# Starlings_Technology_nrf52.net
KiCad netlist of a schematic drawn in EAGLE
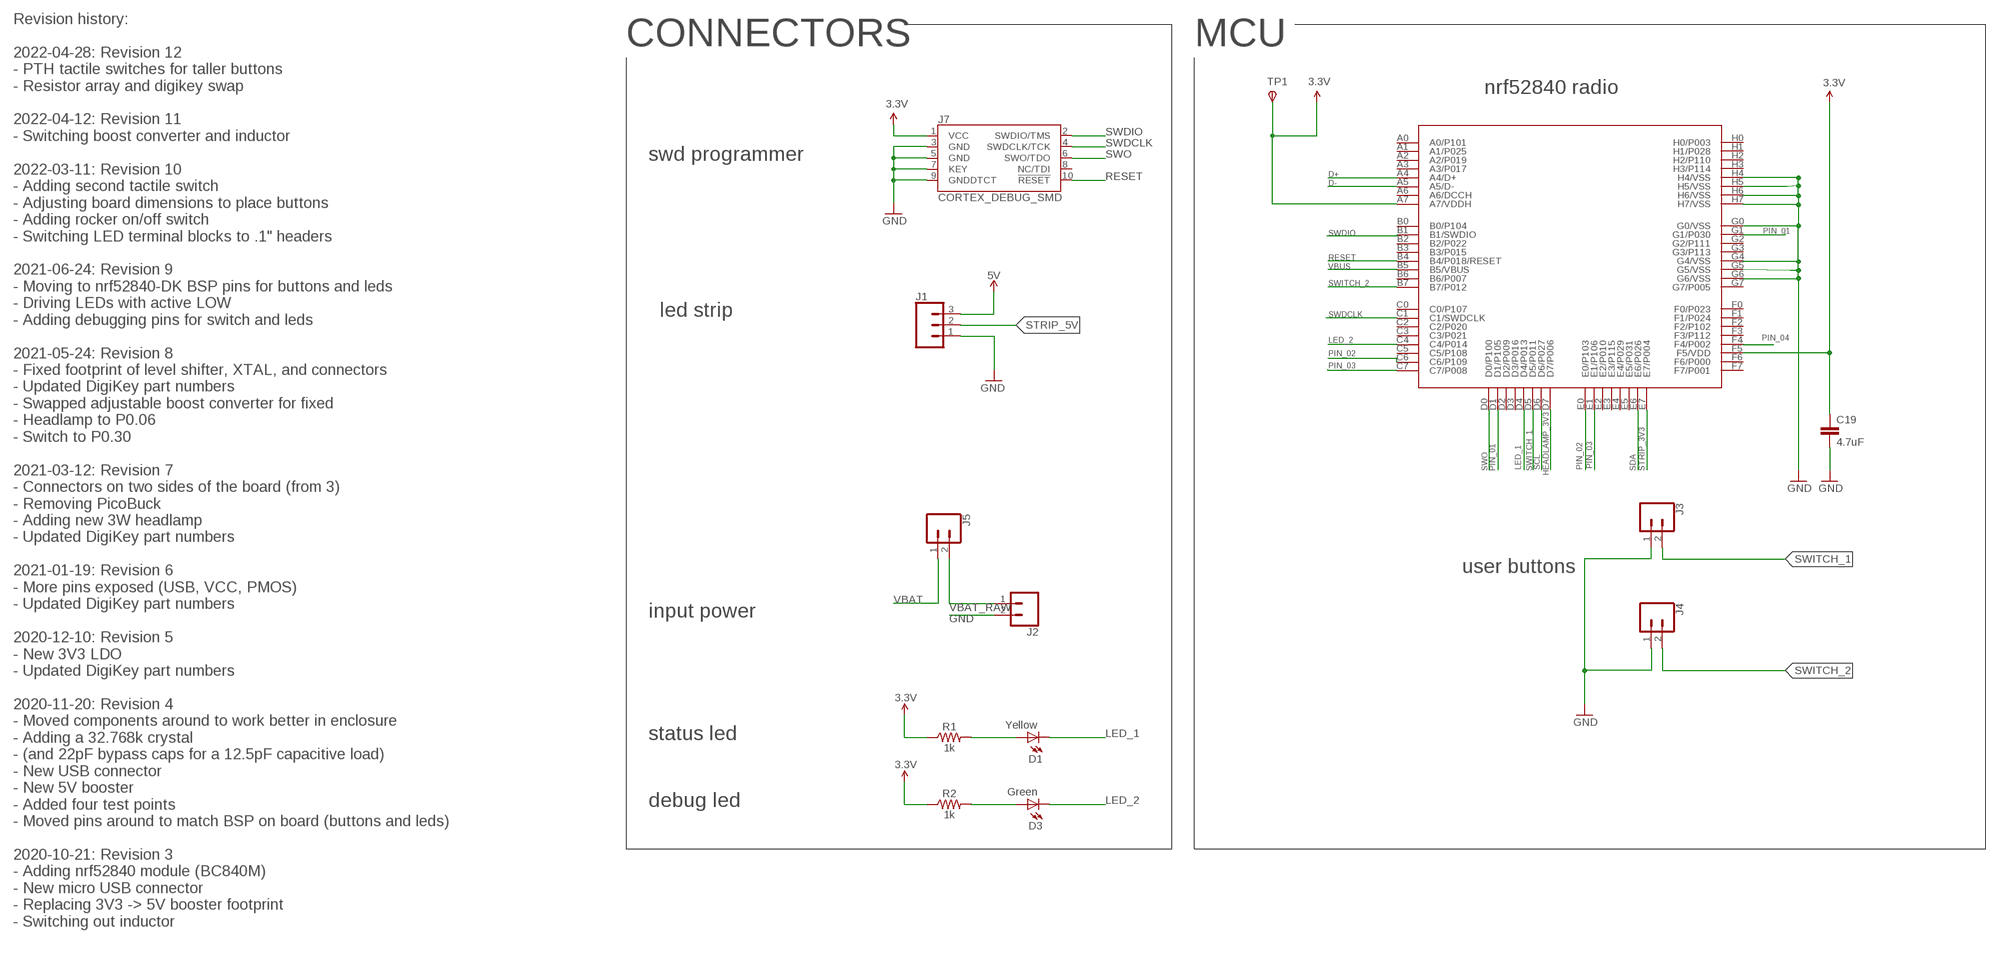
[diagram p0: schematic, sheet 1, part 1 of 2]
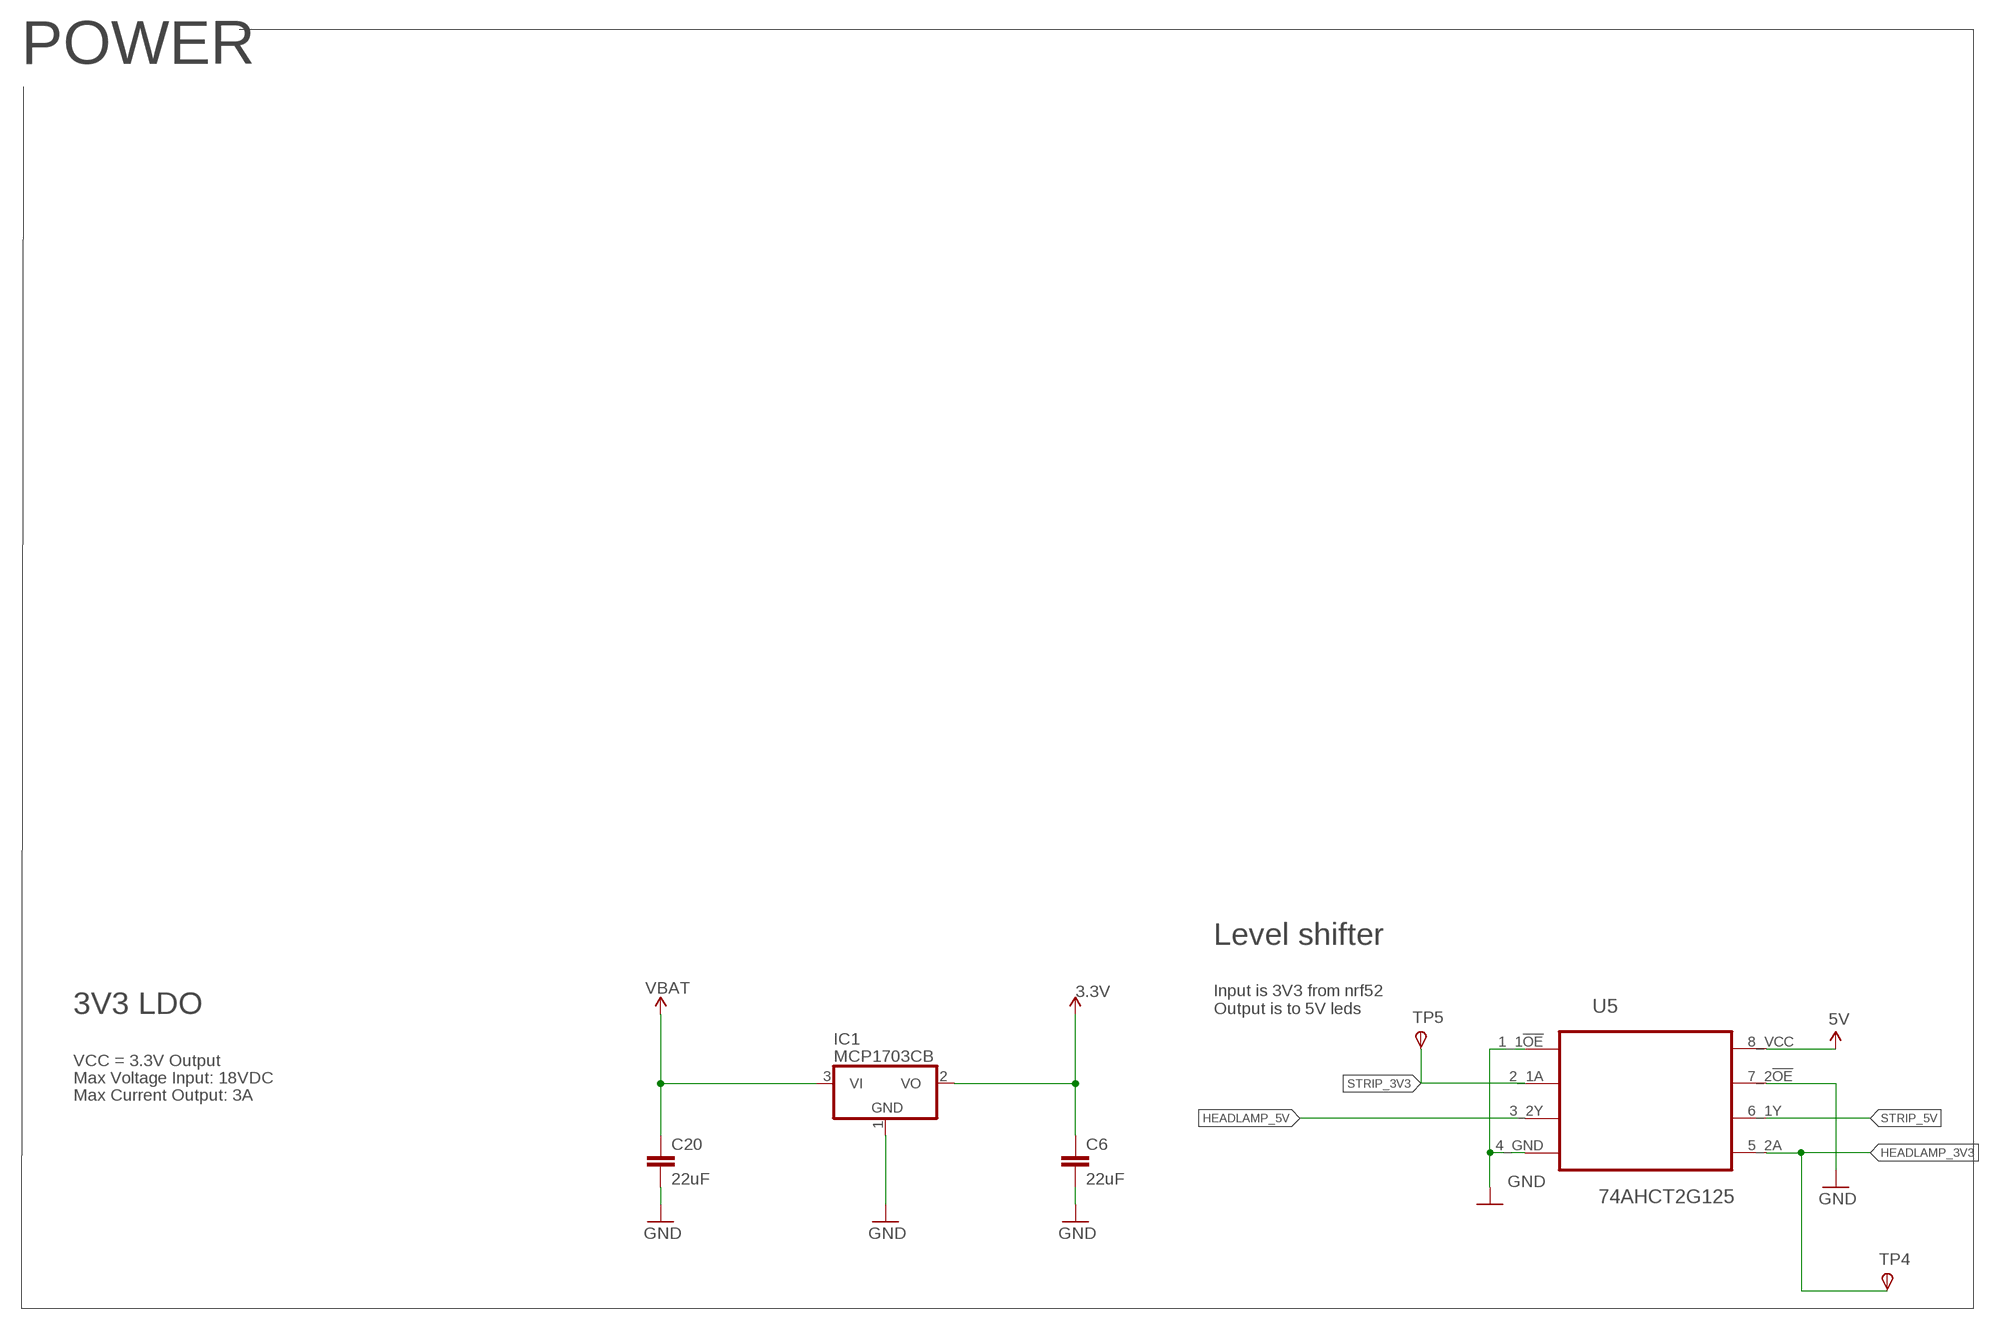
[diagram p1: schematic, sheet 1, part 2 of 2]

(export (version "E")
  (design (tool "Eeschema 10.0.6"))
  (components
    (comp (ref "C6")
      (value "22uF")
      (footprint "eagle-import:0805")
      (libsource (lib "eagle-import") (part "22UF-0805-6.3V-20%"))
    )
    (comp (ref "C19")
      (value "4.7uF")
      (footprint "eagle-import:0603")
      (libsource (lib "eagle-import") (part "4.7UF0603"))
    )
    (comp (ref "C20")
      (value "22uF")
      (footprint "eagle-import:0805")
      (libsource (lib "eagle-import") (part "22UF-0805-6.3V-20%"))
    )
    (comp (ref "D1")
      (value "Yellow")
      (footprint "eagle-import:LED-0603")
      (libsource (lib "eagle-import") (part "LED0603"))
    )
    (comp (ref "D3")
      (value "Green")
      (footprint "eagle-import:LED-0603")
      (libsource (lib "eagle-import") (part "LED0603"))
    )
    (comp (ref "IC1")
      (value "MCP1703CB")
      (footprint "eagle-import:SOT23")
      (libsource (lib "eagle-import") (part "MCP1703CB"))
    )
    (comp (ref "J1")
      (value "CONN_03LOCK_LONGPADS")
      (footprint "eagle-import:1X03_LOCK_LONGPADS")
      (libsource (lib "eagle-import") (part "CONN_03LOCK_LONGPADS"))
    )
    (comp (ref "J2")
      (value "CONN_02LOCK_LONGPADS")
      (footprint "eagle-import:1X02_LOCK_LONGPADS")
      (libsource (lib "eagle-import") (part "CONN_02LOCK_LONGPADS"))
    )
    (comp (ref "J3")
      (value "CONN_02LOCK_LONGPADS")
      (footprint "eagle-import:1X02_LOCK_LONGPADS")
      (libsource (lib "eagle-import") (part "CONN_02LOCK_LONGPADS"))
    )
    (comp (ref "J4")
      (value "CONN_02LOCK_LONGPADS")
      (footprint "eagle-import:1X02_LOCK_LONGPADS")
      (libsource (lib "eagle-import") (part "CONN_02LOCK_LONGPADS"))
    )
    (comp (ref "J5")
      (value "CONN_02LOCK_LONGPADS")
      (footprint "eagle-import:1X02_LOCK_LONGPADS")
      (libsource (lib "eagle-import") (part "CONN_02LOCK_LONGPADS"))
    )
    (comp (ref "J7")
      (value "CORTEX_DEBUG_SMD")
      (footprint "eagle-import:SAMTECH_FTSH-105-01")
      (libsource (lib "eagle-import") (part "CORTEX_DEBUG_SMD"))
    )
    (comp (ref "R1")
      (value "1k")
      (footprint "eagle-import:0603")
      (libsource (lib "eagle-import") (part "1KOHM-0603-1/10W-1%"))
    )
    (comp (ref "R2")
      (value "1k")
      (footprint "eagle-import:0603")
      (libsource (lib "eagle-import") (part "1KOHM-0603-1/10W-1%"))
    )
    (comp (ref "TP1")
      (value "TPSB1,27")
      (footprint "eagle-import:B1,27")
      (libsource (lib "eagle-import") (part "TPSB1,27"))
    )
    (comp (ref "TP4")
      (value "TPSB1,27")
      (footprint "eagle-import:B1,27")
      (libsource (lib "eagle-import") (part "TPSB1,27"))
    )
    (comp (ref "TP5")
      (value "TPSB1,27")
      (footprint "eagle-import:B1,27")
      (libsource (lib "eagle-import") (part "TPSB1,27"))
    )
    (comp (ref "U3")
      (value "BC840M")
      (footprint "eagle-import:BC840M")
      (libsource (lib "eagle-import") (part "BC840M"))
    )
    (comp (ref "U5")
      (value "74AHCT2G125")
      (footprint "eagle-import:VSSOP-8")
      (fields (field (name "MPN") "PCA9306DC,125"))
      (libsource (lib "eagle-import") (part "VSSOP-8_DEVICE"))
    )
  )
  (nets
    (net (code "1") (name "/D+") (class "Default")
      (node (ref "U3") (pin "A4") (pinfunction "A4/D+_A4") (pintype "bidirectional"))
    )
    (net (code "2") (name "/D-") (class "Default")
      (node (ref "U3") (pin "A5") (pinfunction "A5/D-_A5") (pintype "bidirectional"))
    )
    (net (code "3") (name "/LED_1") (class "Default")
      (node (ref "D1") (pin "C") (pinfunction "C_C") (pintype "passive"))
      (node (ref "U3") (pin "D4") (pinfunction "D4/P013_D4") (pintype "bidirectional"))
    )
    (net (code "4") (name "/LED_2") (class "Default")
      (node (ref "D3") (pin "C") (pinfunction "C_C") (pintype "passive"))
      (node (ref "U3") (pin "C4") (pinfunction "C4/P014_C4") (pintype "bidirectional"))
    )
    (net (code "5") (name "/PIN_01") (class "Default")
      (node (ref "U3") (pin "D1") (pinfunction "D1/P105_D1") (pintype "bidirectional"))
      (node (ref "U3") (pin "G1") (pinfunction "G1/P030_G1") (pintype "bidirectional"))
    )
    (net (code "6") (name "/PIN_02") (class "Default")
      (node (ref "U3") (pin "C6") (pinfunction "C6/P109_C6") (pintype "bidirectional"))
      (node (ref "U3") (pin "E0") (pinfunction "E0/P103_E0") (pintype "bidirectional"))
    )
    (net (code "7") (name "/PIN_03") (class "Default")
      (node (ref "U3") (pin "C7") (pinfunction "C7/P008_C7") (pintype "bidirectional"))
      (node (ref "U3") (pin "E1") (pinfunction "E1/P106_E1") (pintype "bidirectional"))
    )
    (net (code "8") (name "/PIN_04") (class "Default")
      (node (ref "U3") (pin "F4") (pinfunction "F4/P002_F4") (pintype "bidirectional"))
    )
    (net (code "9") (name "/RESET") (class "Default")
      (node (ref "J7") (pin "10") (pinfunction "~{RESET}_10") (pintype "bidirectional"))
      (node (ref "U3") (pin "B4") (pinfunction "B4/P018/RESET_B4") (pintype "bidirectional"))
    )
    (net (code "10") (name "/SCL") (class "Default")
      (node (ref "U3") (pin "D6") (pinfunction "D6/P027_D6") (pintype "bidirectional"))
    )
    (net (code "11") (name "/SDA") (class "Default")
      (node (ref "U3") (pin "E6") (pinfunction "E6/P026_E6") (pintype "bidirectional"))
    )
    (net (code "12") (name "/SWDCLK") (class "Default")
      (node (ref "J7") (pin "4") (pinfunction "SWDCLK/TCK_4") (pintype "bidirectional"))
      (node (ref "U3") (pin "C1") (pinfunction "C1/SWDCLK_C1") (pintype "bidirectional"))
    )
    (net (code "13") (name "/SWDIO") (class "Default")
      (node (ref "J7") (pin "2") (pinfunction "SWDIO/TMS_2") (pintype "bidirectional"))
      (node (ref "U3") (pin "B1") (pinfunction "B1/SWDIO_B1") (pintype "bidirectional"))
    )
    (net (code "14") (name "/SWO") (class "Default")
      (node (ref "J7") (pin "6") (pinfunction "SWO/TDO_6") (pintype "bidirectional"))
      (node (ref "U3") (pin "D0") (pinfunction "D0/P100_D0") (pintype "bidirectional"))
    )
    (net (code "15") (name "/VBAT_RAW") (class "Default")
      (node (ref "J2") (pin "1") (pinfunction "1_1") (pintype "passive"))
      (node (ref "J5") (pin "2") (pinfunction "2_2") (pintype "passive"))
    )
    (net (code "16") (name "/VBUS") (class "Default")
      (node (ref "U3") (pin "B5") (pinfunction "B5/VBUS_B5") (pintype "bidirectional"))
    )
    (net (code "17") (name "3.3V") (class "Default")
      (node (ref "C19") (pin "1") (pinfunction "1_1") (pintype "passive"))
      (node (ref "C6") (pin "1") (pinfunction "1_1") (pintype "passive"))
      (node (ref "IC1") (pin "2") (pinfunction "VO_2") (pintype "passive"))
      (node (ref "J7") (pin "1") (pinfunction "VCC_1") (pintype "bidirectional"))
      (node (ref "R1") (pin "1") (pinfunction "1_1") (pintype "passive"))
      (node (ref "R2") (pin "1") (pinfunction "1_1") (pintype "passive"))
      (node (ref "TP1") (pin "TP") (pinfunction "PP_TP") (pintype "input"))
      (node (ref "U3") (pin "A7") (pinfunction "A7/VDDH_A7") (pintype "bidirectional"))
      (node (ref "U3") (pin "F5") (pinfunction "F5/VDD_F5") (pintype "bidirectional"))
    )
    (net (code "18") (name "5V") (class "Default")
      (node (ref "J1") (pin "3") (pinfunction "3_3") (pintype "passive"))
      (node (ref "U5") (pin "8_VCC") (pinfunction "8_8_VCC") (pintype "bidirectional"))
    )
    (net (code "19") (name "GND") (class "Default")
      (node (ref "C19") (pin "2") (pinfunction "2_2") (pintype "passive"))
      (node (ref "C20") (pin "2") (pinfunction "2_2") (pintype "passive"))
      (node (ref "C6") (pin "2") (pinfunction "2_2") (pintype "passive"))
      (node (ref "IC1") (pin "1") (pinfunction "GND_1") (pintype "passive"))
      (node (ref "J1") (pin "1") (pinfunction "1_1") (pintype "passive"))
      (node (ref "J2") (pin "2") (pinfunction "2_2") (pintype "passive"))
      (node (ref "J3") (pin "1") (pinfunction "1_1") (pintype "passive"))
      (node (ref "J4") (pin "1") (pinfunction "1_1") (pintype "passive"))
      (node (ref "J7") (pin "3") (pinfunction "GND_3") (pintype "bidirectional"))
      (node (ref "J7") (pin "5") (pinfunction "GND_5") (pintype "bidirectional"))
      (node (ref "J7") (pin "7") (pinfunction "KEY_7") (pintype "bidirectional"))
      (node (ref "J7") (pin "9") (pinfunction "GNDDTCT_9") (pintype "bidirectional"))
      (node (ref "U3") (pin "G0") (pinfunction "G0/VSS_G0") (pintype "bidirectional"))
      (node (ref "U3") (pin "G4") (pinfunction "G4/VSS_G4") (pintype "bidirectional"))
      (node (ref "U3") (pin "G5") (pinfunction "G5/VSS_G5") (pintype "bidirectional"))
      (node (ref "U3") (pin "G6") (pinfunction "G6/VSS_G6") (pintype "bidirectional"))
      (node (ref "U3") (pin "H4") (pinfunction "H4/VSS_H4") (pintype "bidirectional"))
      (node (ref "U3") (pin "H5") (pinfunction "H5/VSS_H5") (pintype "bidirectional"))
      (node (ref "U3") (pin "H6") (pinfunction "H6/VSS_H6") (pintype "bidirectional"))
      (node (ref "U3") (pin "H7") (pinfunction "H7/VSS_H7") (pintype "bidirectional"))
      (node (ref "U5") (pin "1_1!OE") (pinfunction "1_1_1!OE") (pintype "bidirectional"))
      (node (ref "U5") (pin "4_GND") (pinfunction "4_4_GND") (pintype "bidirectional"))
      (node (ref "U5") (pin "7_2!OE") (pinfunction "7_7_2!OE") (pintype "bidirectional"))
    )
    (net (code "20") (name "HEADLAMP_3V3") (class "Default")
      (node (ref "TP4") (pin "TP") (pinfunction "PP_TP") (pintype "input"))
      (node (ref "U3") (pin "D7") (pinfunction "D7/P006_D7") (pintype "bidirectional"))
      (node (ref "U5") (pin "5_2A") (pinfunction "5_5_2A") (pintype "bidirectional"))
    )
    (net (code "21") (name "HEADLAMP_5V") (class "Default")
      (node (ref "U5") (pin "3_2Y") (pinfunction "3_3_2Y") (pintype "bidirectional"))
    )
    (net (code "22") (name "Net-(D1-PadA)") (class "Default")
      (node (ref "D1") (pin "A") (pinfunction "A_A") (pintype "passive"))
      (node (ref "R1") (pin "2") (pinfunction "2_2") (pintype "passive"))
    )
    (net (code "23") (name "Net-(D3-PadA)") (class "Default")
      (node (ref "D3") (pin "A") (pinfunction "A_A") (pintype "passive"))
      (node (ref "R2") (pin "2") (pinfunction "2_2") (pintype "passive"))
    )
    (net (code "24") (name "STRIP_3V3") (class "Default")
      (node (ref "TP5") (pin "TP") (pinfunction "PP_TP") (pintype "input"))
      (node (ref "U3") (pin "E7") (pinfunction "E7/P004_E7") (pintype "bidirectional"))
      (node (ref "U5") (pin "2_1A") (pinfunction "2_2_1A") (pintype "bidirectional"))
    )
    (net (code "25") (name "STRIP_5V") (class "Default")
      (node (ref "J1") (pin "2") (pinfunction "2_2") (pintype "passive"))
      (node (ref "U5") (pin "6_1Y") (pinfunction "6_6_1Y") (pintype "bidirectional"))
    )
    (net (code "26") (name "SWITCH_1") (class "Default")
      (node (ref "J3") (pin "2") (pinfunction "2_2") (pintype "passive"))
      (node (ref "U3") (pin "D5") (pinfunction "D5/P011_D5") (pintype "bidirectional"))
    )
    (net (code "27") (name "SWITCH_2") (class "Default")
      (node (ref "J4") (pin "2") (pinfunction "2_2") (pintype "passive"))
      (node (ref "U3") (pin "B7") (pinfunction "B7/P012_B7") (pintype "bidirectional"))
    )
    (net (code "28") (name "VBAT") (class "Default")
      (node (ref "C20") (pin "1") (pinfunction "1_1") (pintype "passive"))
      (node (ref "IC1") (pin "3") (pinfunction "VI_3") (pintype "input"))
      (node (ref "J5") (pin "1") (pinfunction "1_1") (pintype "passive"))
    )
    (net (code "29") (name "unconnected-(J7-NC{slash}TDI-Pad8)") (class "Default")
      (node (ref "J7") (pin "8") (pinfunction "NC/TDI_8") (pintype "bidirectional"))
    )
    (net (code "30") (name "unconnected-(U3-A0{slash}P101-PadA0)") (class "Default")
      (node (ref "U3") (pin "A0") (pinfunction "A0/P101_A0") (pintype "bidirectional"))
    )
    (net (code "31") (name "unconnected-(U3-A1{slash}P025-PadA1)") (class "Default")
      (node (ref "U3") (pin "A1") (pinfunction "A1/P025_A1") (pintype "bidirectional"))
    )
    (net (code "32") (name "unconnected-(U3-A2{slash}P019-PadA2)") (class "Default")
      (node (ref "U3") (pin "A2") (pinfunction "A2/P019_A2") (pintype "bidirectional"))
    )
    (net (code "33") (name "unconnected-(U3-A3{slash}P017-PadA3)") (class "Default")
      (node (ref "U3") (pin "A3") (pinfunction "A3/P017_A3") (pintype "bidirectional"))
    )
    (net (code "34") (name "unconnected-(U3-A6{slash}DCCH-PadA6)") (class "Default")
      (node (ref "U3") (pin "A6") (pinfunction "A6/DCCH_A6") (pintype "bidirectional"))
    )
    (net (code "35") (name "unconnected-(U3-B0{slash}P104-PadB0)") (class "Default")
      (node (ref "U3") (pin "B0") (pinfunction "B0/P104_B0") (pintype "bidirectional"))
    )
    (net (code "36") (name "unconnected-(U3-B2{slash}P022-PadB2)") (class "Default")
      (node (ref "U3") (pin "B2") (pinfunction "B2/P022_B2") (pintype "bidirectional"))
    )
    (net (code "37") (name "unconnected-(U3-B3{slash}P015-PadB3)") (class "Default")
      (node (ref "U3") (pin "B3") (pinfunction "B3/P015_B3") (pintype "bidirectional"))
    )
    (net (code "38") (name "unconnected-(U3-B6{slash}P007-PadB6)") (class "Default")
      (node (ref "U3") (pin "B6") (pinfunction "B6/P007_B6") (pintype "bidirectional"))
    )
    (net (code "39") (name "unconnected-(U3-C0{slash}P107-PadC0)") (class "Default")
      (node (ref "U3") (pin "C0") (pinfunction "C0/P107_C0") (pintype "bidirectional"))
    )
    (net (code "40") (name "unconnected-(U3-C2{slash}P020-PadC2)") (class "Default")
      (node (ref "U3") (pin "C2") (pinfunction "C2/P020_C2") (pintype "bidirectional"))
    )
    (net (code "41") (name "unconnected-(U3-C3{slash}P021-PadC3)") (class "Default")
      (node (ref "U3") (pin "C3") (pinfunction "C3/P021_C3") (pintype "bidirectional"))
    )
    (net (code "42") (name "unconnected-(U3-C5{slash}P108-PadC5)") (class "Default")
      (node (ref "U3") (pin "C5") (pinfunction "C5/P108_C5") (pintype "bidirectional"))
    )
    (net (code "43") (name "unconnected-(U3-D2{slash}P009-PadD2)") (class "Default")
      (node (ref "U3") (pin "D2") (pinfunction "D2/P009_D2") (pintype "bidirectional"))
    )
    (net (code "44") (name "unconnected-(U3-D3{slash}P016-PadD3)") (class "Default")
      (node (ref "U3") (pin "D3") (pinfunction "D3/P016_D3") (pintype "bidirectional"))
    )
    (net (code "45") (name "unconnected-(U3-E2{slash}P010-PadE2)") (class "Default")
      (node (ref "U3") (pin "E2") (pinfunction "E2/P010_E2") (pintype "bidirectional"))
    )
    (net (code "46") (name "unconnected-(U3-E3{slash}P115-PadE3)") (class "Default")
      (node (ref "U3") (pin "E3") (pinfunction "E3/P115_E3") (pintype "bidirectional"))
    )
    (net (code "47") (name "unconnected-(U3-E4{slash}P029-PadE4)") (class "Default")
      (node (ref "U3") (pin "E4") (pinfunction "E4/P029_E4") (pintype "bidirectional"))
    )
    (net (code "48") (name "unconnected-(U3-E5{slash}P031-PadE5)") (class "Default")
      (node (ref "U3") (pin "E5") (pinfunction "E5/P031_E5") (pintype "bidirectional"))
    )
    (net (code "49") (name "unconnected-(U3-F0{slash}P023-PadF0)") (class "Default")
      (node (ref "U3") (pin "F0") (pinfunction "F0/P023_F0") (pintype "bidirectional"))
    )
    (net (code "50") (name "unconnected-(U3-F1{slash}P024-PadF1)") (class "Default")
      (node (ref "U3") (pin "F1") (pinfunction "F1/P024_F1") (pintype "bidirectional"))
    )
    (net (code "51") (name "unconnected-(U3-F2{slash}P102-PadF2)") (class "Default")
      (node (ref "U3") (pin "F2") (pinfunction "F2/P102_F2") (pintype "bidirectional"))
    )
    (net (code "52") (name "unconnected-(U3-F3{slash}P112-PadF3)") (class "Default")
      (node (ref "U3") (pin "F3") (pinfunction "F3/P112_F3") (pintype "bidirectional"))
    )
    (net (code "53") (name "unconnected-(U3-F6{slash}P000-PadF6)") (class "Default")
      (node (ref "U3") (pin "F6") (pinfunction "F6/P000_F6") (pintype "bidirectional"))
    )
    (net (code "54") (name "unconnected-(U3-F7{slash}P001-PadF7)") (class "Default")
      (node (ref "U3") (pin "F7") (pinfunction "F7/P001_F7") (pintype "bidirectional"))
    )
    (net (code "55") (name "unconnected-(U3-G2{slash}P111-PadG2)") (class "Default")
      (node (ref "U3") (pin "G2") (pinfunction "G2/P111_G2") (pintype "bidirectional"))
    )
    (net (code "56") (name "unconnected-(U3-G3{slash}P113-PadG3)") (class "Default")
      (node (ref "U3") (pin "G3") (pinfunction "G3/P113_G3") (pintype "bidirectional"))
    )
    (net (code "57") (name "unconnected-(U3-G7{slash}P005-PadG7)") (class "Default")
      (node (ref "U3") (pin "G7") (pinfunction "G7/P005_G7") (pintype "bidirectional"))
    )
    (net (code "58") (name "unconnected-(U3-H0{slash}P003-PadH0)") (class "Default")
      (node (ref "U3") (pin "H0") (pinfunction "H0/P003_H0") (pintype "bidirectional"))
    )
    (net (code "59") (name "unconnected-(U3-H1{slash}P028-PadH1)") (class "Default")
      (node (ref "U3") (pin "H1") (pinfunction "H1/P028_H1") (pintype "bidirectional"))
    )
    (net (code "60") (name "unconnected-(U3-H2{slash}P110-PadH2)") (class "Default")
      (node (ref "U3") (pin "H2") (pinfunction "H2/P110_H2") (pintype "bidirectional"))
    )
    (net (code "61") (name "unconnected-(U3-H3{slash}P114-PadH3)") (class "Default")
      (node (ref "U3") (pin "H3") (pinfunction "H3/P114_H3") (pintype "bidirectional"))
    )
  )
)
